# Phototransistor1.net
KiCad netlist of a schematic drawn in EAGLE
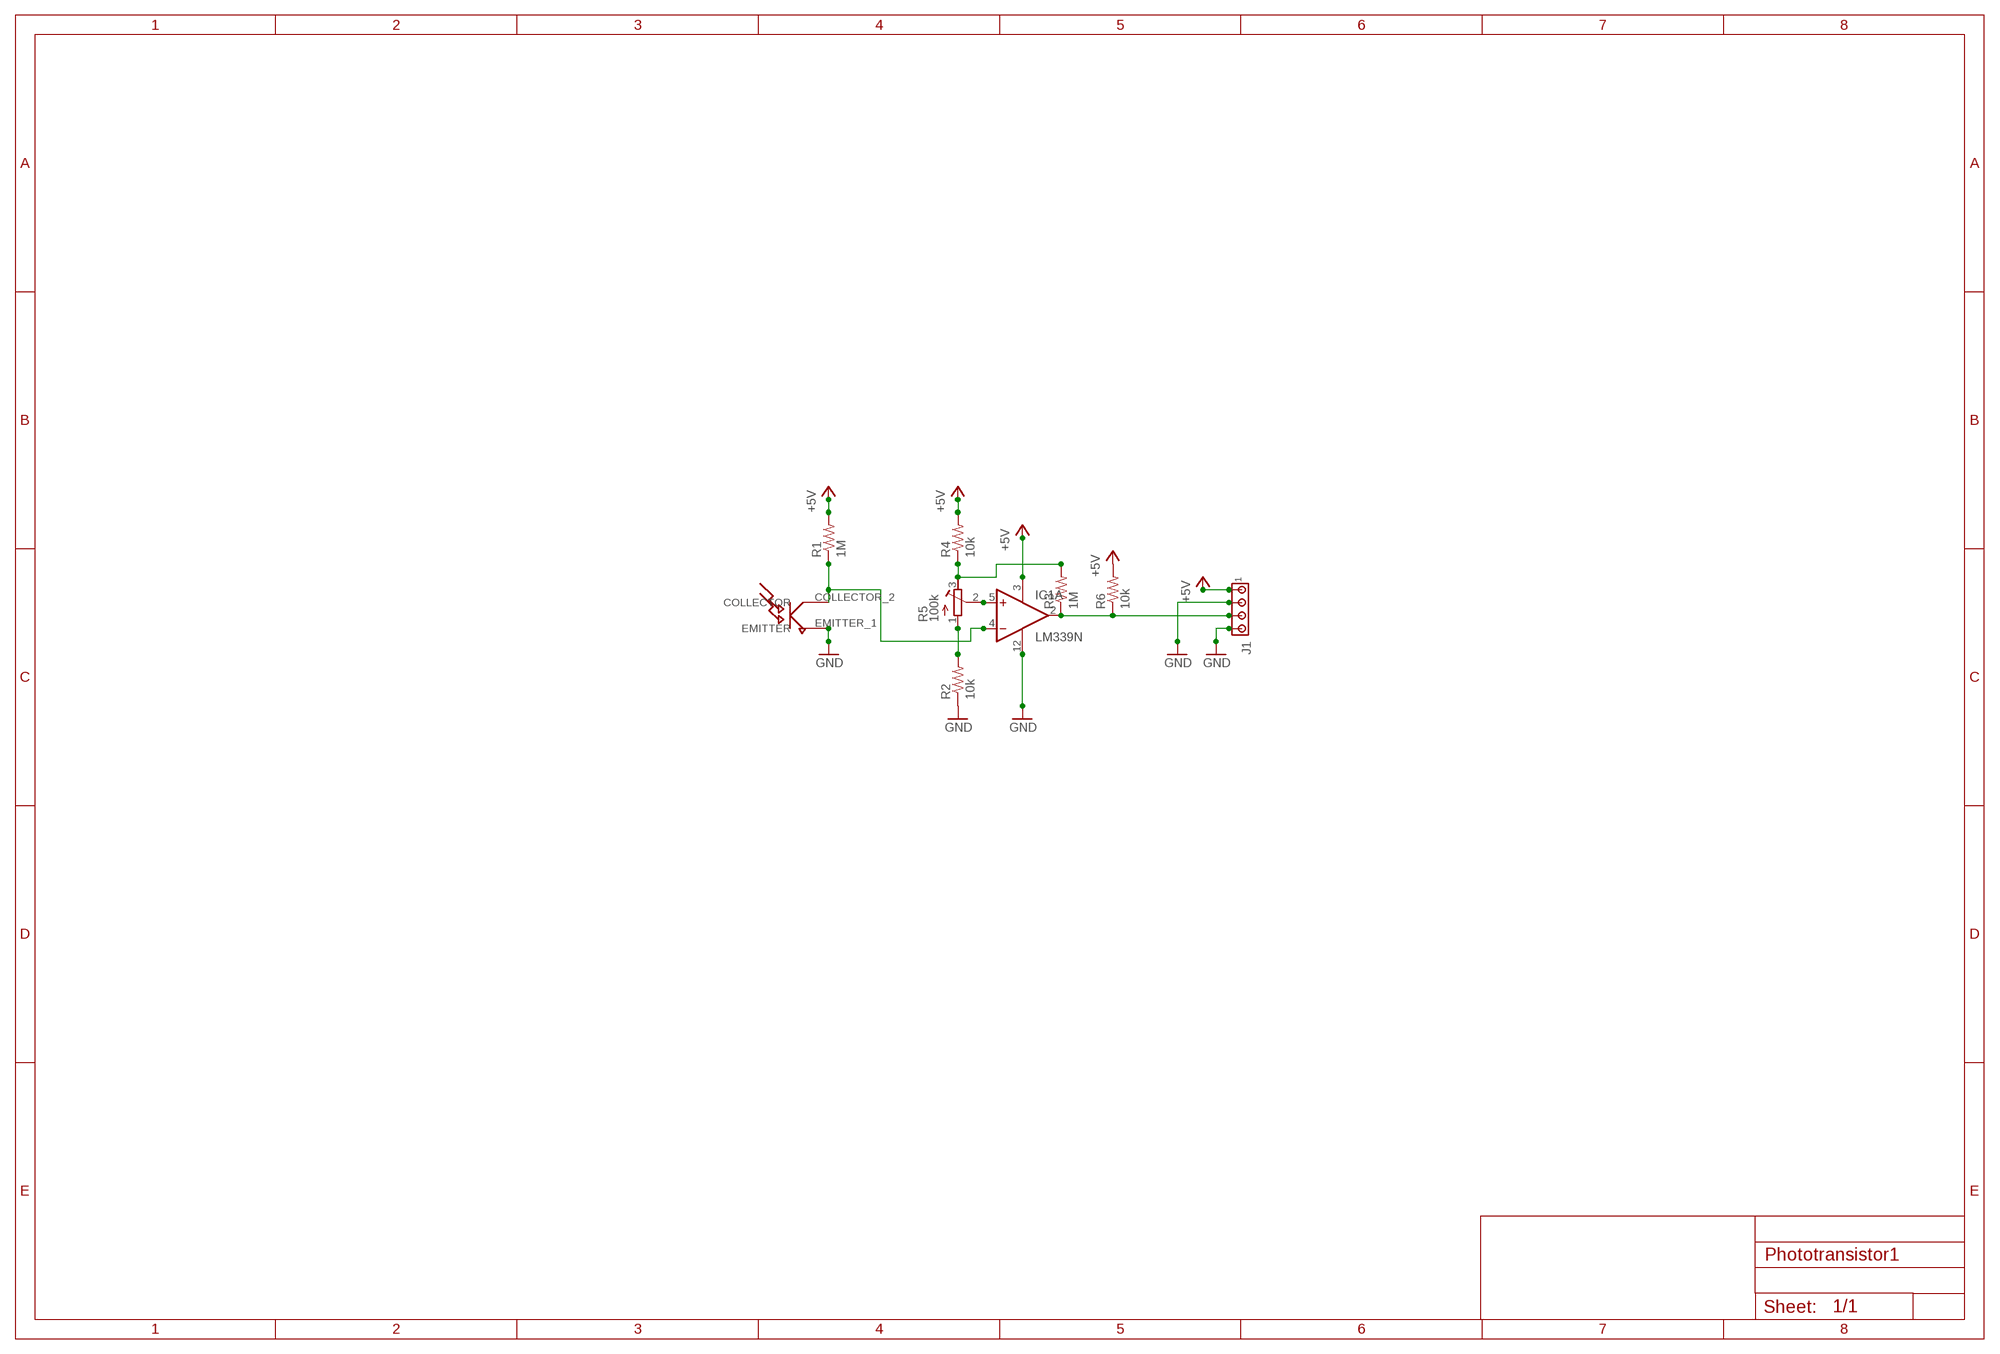
[diagram p0: schematic, sheet 1]

(export (version "E")
  (design (tool "Eeschema 10.0.6"))
  (components
    (comp (ref "IC1")
      (value "LM339N")
      (footprint "eagle-import:DIL14")
      (libsource (lib "eagle-import") (part "LM339N"))
    )
    (comp (ref "J1")
      (value "MTA04-100")
      (footprint "eagle-import:10X04MTA")
      (libsource (lib "eagle-import") (part "MTA04-100"))
    )
    (comp (ref "R1")
      (value "1M")
      (footprint "eagle-import:0204_7")
      (libsource (lib "eagle-import") (part "R-US_0204/7"))
    )
    (comp (ref "R2")
      (value "10k")
      (footprint "eagle-import:0204_7")
      (libsource (lib "eagle-import") (part "R-US_0204/7"))
    )
    (comp (ref "R3")
      (value "1M")
      (footprint "eagle-import:0204_7")
      (libsource (lib "eagle-import") (part "R-US_0204/7"))
    )
    (comp (ref "R4")
      (value "10k")
      (footprint "eagle-import:0204_7")
      (libsource (lib "eagle-import") (part "R-US_0204/7"))
    )
    (comp (ref "R5")
      (value "100k")
      (footprint "eagle-import:RTRIM3296W")
      (libsource (lib "eagle-import") (part "R-TRIMM3296W"))
    )
    (comp (ref "R6")
      (value "10k")
      (footprint "eagle-import:0204_7")
      (libsource (lib "eagle-import") (part "R-US_0204/7"))
    )
    (comp (ref "U$1")
      (value "NTE3034")
      (footprint "eagle-import:NTE3034_")
      (libsource (lib "eagle-import") (part "NTE3034"))
    )
  )
  (nets
    (net (code "1") (name "+5V") (class "Default")
      (node (ref "IC1") (pin "3") (pinfunction "V+_3") (pintype "power_in"))
      (node (ref "J1") (pin "1") (pinfunction "1_1") (pintype "passive"))
      (node (ref "R1") (pin "2") (pinfunction "2_2") (pintype "passive"))
      (node (ref "R4") (pin "2") (pinfunction "2_2") (pintype "passive"))
      (node (ref "R6") (pin "2") (pinfunction "2_2") (pintype "passive"))
    )
    (net (code "2") (name "GND") (class "Default")
      (node (ref "IC1") (pin "12") (pinfunction "GND_12") (pintype "power_in"))
      (node (ref "J1") (pin "2") (pinfunction "2_2") (pintype "passive"))
      (node (ref "J1") (pin "4") (pinfunction "4_4") (pintype "passive"))
      (node (ref "R2") (pin "1") (pinfunction "1_1") (pintype "passive"))
      (node (ref "U$1") (pin "EMITTER_1") (pinfunction "EMITTER_EMITTER_1") (pintype "bidirectional"))
    )
    (net (code "3") (name "Net-(IC1A-+IN)") (class "Default")
      (node (ref "IC1") (pin "5") (pinfunction "+IN_5") (pintype "input"))
      (node (ref "R5") (pin "2") (pinfunction "S_2") (pintype "passive"))
    )
    (net (code "4") (name "Net-(IC1A--IN)") (class "Default")
      (node (ref "IC1") (pin "4") (pinfunction "-IN_4") (pintype "input"))
      (node (ref "R1") (pin "1") (pinfunction "1_1") (pintype "passive"))
      (node (ref "U$1") (pin "COLLECTOR_2") (pinfunction "COLLECTOR_COLLECTOR_2") (pintype "bidirectional"))
    )
    (net (code "5") (name "Net-(IC1A-OUT)") (class "Default")
      (node (ref "IC1") (pin "2") (pinfunction "OUT_2") (pintype "open_collector"))
      (node (ref "J1") (pin "3") (pinfunction "3_3") (pintype "passive"))
      (node (ref "R3") (pin "1") (pinfunction "1_1") (pintype "passive"))
      (node (ref "R6") (pin "1") (pinfunction "1_1") (pintype "passive"))
    )
    (net (code "6") (name "Net-(R5-A)") (class "Default")
      (node (ref "R3") (pin "2") (pinfunction "2_2") (pintype "passive"))
      (node (ref "R4") (pin "1") (pinfunction "1_1") (pintype "passive"))
      (node (ref "R5") (pin "3") (pinfunction "A_3") (pintype "passive"))
    )
    (net (code "7") (name "Net-(R5-E)") (class "Default")
      (node (ref "R2") (pin "2") (pinfunction "2_2") (pintype "passive"))
      (node (ref "R5") (pin "1") (pinfunction "E_1") (pintype "passive"))
    )
  )
)
